# LKS_074DO.net
KiCad netlist of a schematic drawn in Altium Designer
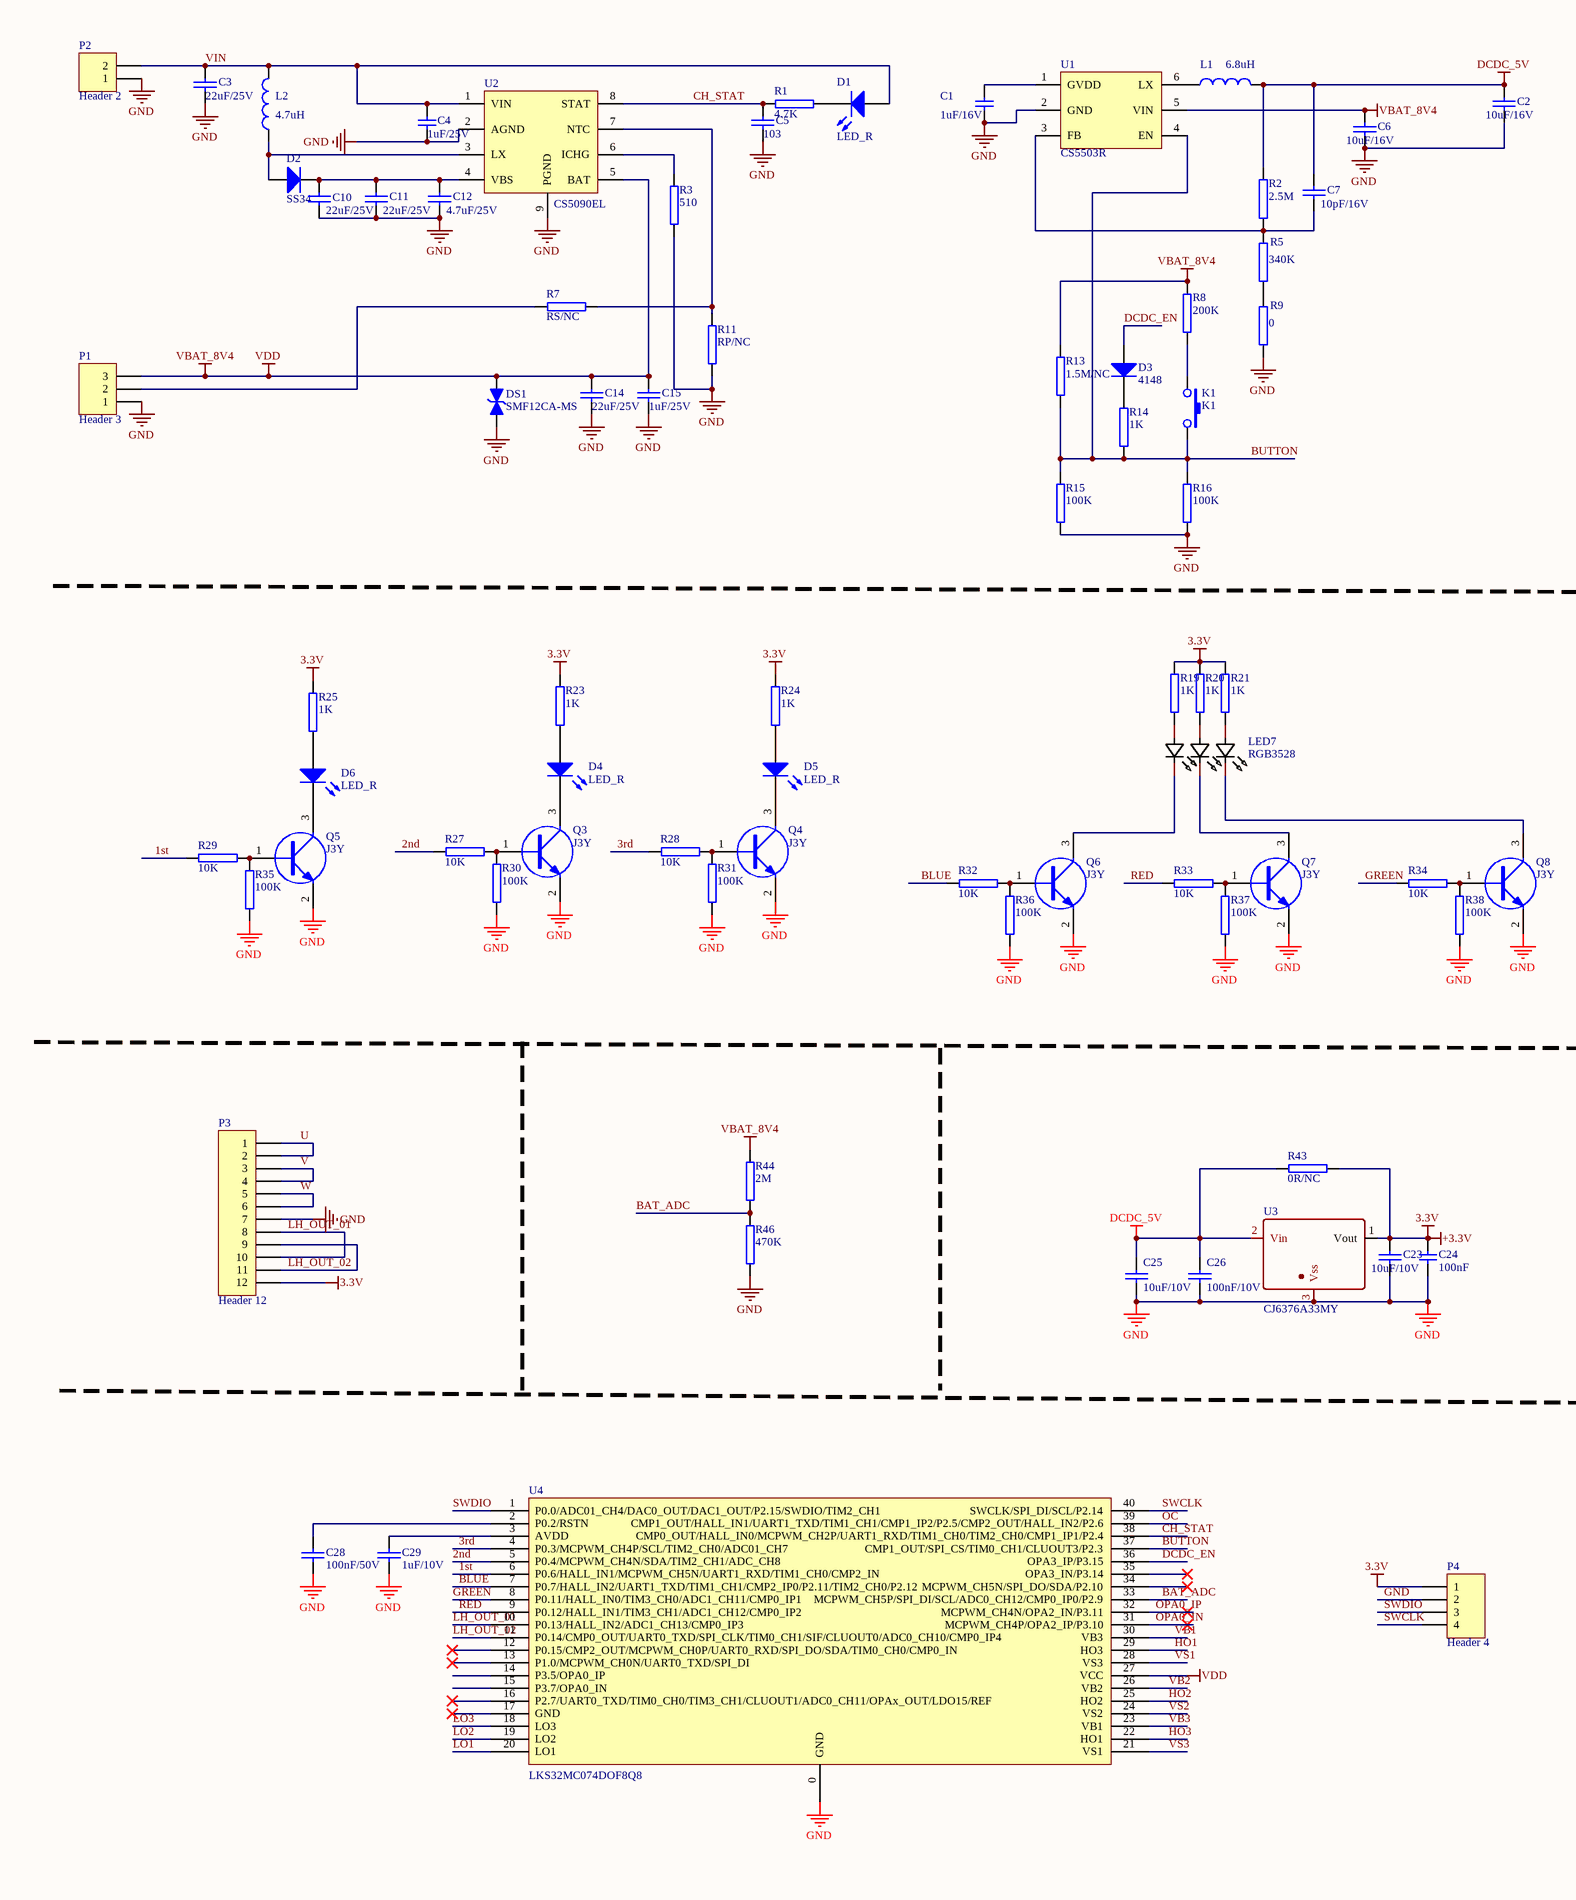
[diagram p0: LKS_074DO.SchDoc, left]
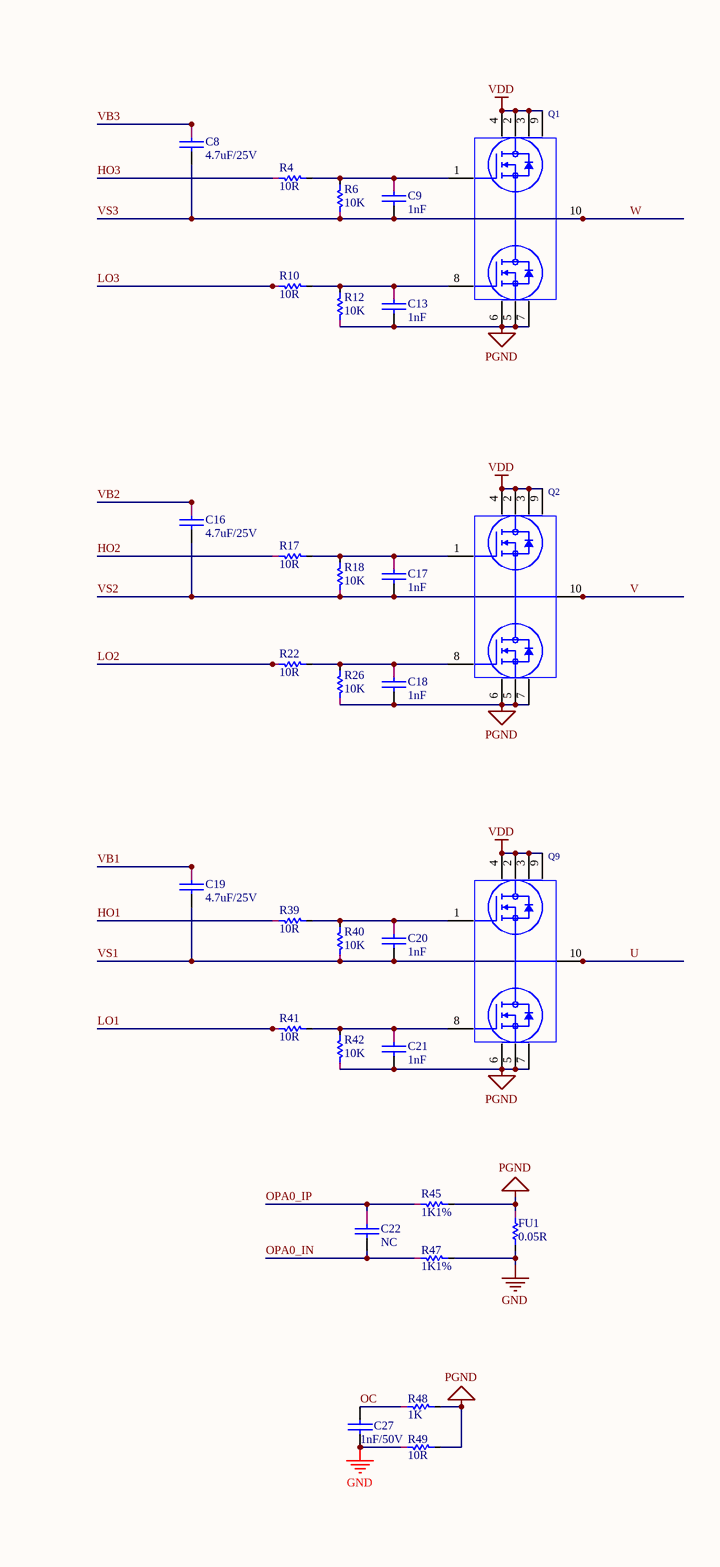
[diagram p1: LKS_074DO.SchDoc, right]

(export (version "E")
  (design (tool "Eeschema 10.0.6"))
  (components
    (comp (ref "C1") (value "1uF/16V") (footprint "C 0402_M") (libsource (lib "") (part "CAP_2")))
    (comp (ref "C2")
      (value "10uF/16V")
      (footprint "0805C")
      (description "Capacitor")
      (libsource (lib "") (part "CAP_1"))
    )
    (comp (ref "C3")
      (value "22uF/25V")
      (footprint "0805C")
      (description "Capacitor")
      (libsource (lib "") (part "CAP_1"))
    )
    (comp (ref "C4") (value "1uF/25V") (footprint "C 0402_M") (libsource (lib "") (part "CAP_2")))
    (comp (ref "C5")
      (value "103")
      (footprint "R 0402_M")
      (description "Capacitor")
      (libsource (lib "") (part "CAP_1"))
    )
    (comp (ref "C6")
      (value "10uF/16V")
      (footprint "0805C")
      (description "Capacitor")
      (libsource (lib "") (part "CAP_1"))
    )
    (comp (ref "C7")
      (value "10pF/16V")
      (footprint "C 0402_M")
      (description "Capacitor")
      (libsource (lib "") (part "CAP_1"))
    )
    (comp (ref "C8")
      (value "4.7uF/25V")
      (footprint "C 0603_M")
      (description "Capacitor")
      (libsource (lib "*") (part "CAP"))
    )
    (comp (ref "C9")
      (value "1nF")
      (footprint "C 0402_M")
      (description "Capacitor")
      (libsource (lib "*") (part "CAP"))
    )
    (comp (ref "C10")
      (value "22uF/25V")
      (footprint "0805C")
      (description "Capacitor")
      (libsource (lib "") (part "CAP_1"))
    )
    (comp (ref "C11")
      (value "22uF/25V")
      (footprint "0805C")
      (description "Capacitor")
      (libsource (lib "") (part "CAP_1"))
    )
    (comp (ref "C12")
      (value "4.7uF/25V")
      (footprint "C 0402_M")
      (description "Capacitor")
      (libsource (lib "") (part "CAP_1"))
    )
    (comp (ref "C13")
      (value "1nF")
      (footprint "C 0402_M")
      (description "Capacitor")
      (libsource (lib "*") (part "CAP"))
    )
    (comp (ref "C14")
      (value "22uF/25V")
      (footprint "0805C")
      (description "Capacitor")
      (libsource (lib "") (part "CAP_1"))
    )
    (comp (ref "C15")
      (value "1uF/25V")
      (footprint "C 0402_M")
      (description "Capacitor")
      (libsource (lib "") (part "CAP_1"))
    )
    (comp (ref "C16")
      (value "4.7uF/25V")
      (footprint "C 0603_M")
      (description "Capacitor")
      (libsource (lib "*") (part "CAP"))
    )
    (comp (ref "C17")
      (value "1nF")
      (footprint "C 0402_M")
      (description "Capacitor")
      (libsource (lib "*") (part "CAP"))
    )
    (comp (ref "C18")
      (value "1nF")
      (footprint "C 0402_M")
      (description "Capacitor")
      (libsource (lib "*") (part "CAP"))
    )
    (comp (ref "C19")
      (value "4.7uF/25V")
      (footprint "C 0603_M")
      (description "Capacitor")
      (libsource (lib "*") (part "CAP"))
    )
    (comp (ref "C20")
      (value "1nF")
      (footprint "C 0402_M")
      (description "Capacitor")
      (libsource (lib "*") (part "CAP"))
    )
    (comp (ref "C21")
      (value "1nF")
      (footprint "C 0402_M")
      (description "Capacitor")
      (libsource (lib "*") (part "CAP"))
    )
    (comp (ref "C22")
      (value "NC")
      (footprint "C 0402_M")
      (description "Capacitor")
      (libsource (lib "*") (part "CAP"))
    )
    (comp (ref "C23")
      (value "10uF/10V")
      (footprint "0805C")
      (description "Capacitor")
      (libsource (lib "") (part "CAP_1"))
    )
    (comp (ref "C24") (value "100nF") (footprint "C 0402_M") (libsource (lib "") (part "CAP_2")))
    (comp (ref "C25")
      (value "10uF/10V")
      (footprint "0805C")
      (description "Capacitor")
      (libsource (lib "") (part "CAP_1"))
    )
    (comp (ref "C26")
      (value "100nF/10V")
      (footprint "C 0402_M")
      (description "Capacitor")
      (libsource (lib "") (part "CAP_1"))
    )
    (comp (ref "C27")
      (value "1nF/50V")
      (footprint "C 0402_M")
      (description "Capacitor")
      (libsource (lib "*") (part "C"))
    )
    (comp (ref "C28")
      (value "100nF/50V")
      (footprint "C 0402_M")
      (description "Capacitor")
      (libsource (lib "*") (part "C"))
    )
    (comp (ref "C29")
      (value "1uF/10V")
      (footprint "0603")
      (description "Capacitor")
      (libsource (lib "*") (part "C"))
    )
    (comp (ref "D1") (value "LED_R") (footprint "0603-LED") (libsource (lib "PuXun1") (part "LED")))
    (comp (ref "D2")
      (value "SS34")
      (footprint "SOD123FL")
      (description "Default Diode")
      (fields (field (name "PUBLISHER") "Altium Limited"))
      (libsource (lib "LKS034DO_Motor_0520_1") (part "Diode"))
    )
    (comp (ref "D3")
      (value "4148")
      (footprint "SOD-323")
      (description "Default Diode")
      (fields (field (name "PUBLISHER") "Altium Limited"))
      (libsource (lib "LKS034DO_Motor_0520_1") (part "Diode"))
    )
    (comp (ref "D4") (value "LED_R") (footprint "0603-LED") (libsource (lib "PuXun1") (part "LED")))
    (comp (ref "D5") (value "LED_R") (footprint "0603-LED") (libsource (lib "PuXun1") (part "LED")))
    (comp (ref "D6") (value "LED_R") (footprint "0603-LED") (libsource (lib "PuXun1") (part "LED")))
    (comp (ref "DS1")
      (value "SMF12CA-MS")
      (footprint "SOD-123F")
      (description "12V/19.9V")
      (libsource (lib "*") (part "DIODE-3"))
    )
    (comp (ref "FU1") (value "0.05R") (footprint "R 0805_M") (libsource (lib "*") (part "RAS")))
    (comp (ref "K1") (value "K1") (footprint "Button3x4x2") (libsource (lib "SCHLIB_NEW") (part "K1")))
    (comp (ref "L1")
      (value "6.8uH")
      (footprint "SMD3X3")
      (description "Inductor")
      (fields (field (name "PUBLISHER") "Altium Limited"))
      (libsource (lib "Miscellaneous Devices") (part "Inductor"))
    )
    (comp (ref "L2")
      (value "4.7uH")
      (footprint "0420-L")
      (description "Inductor")
      (fields (field (name "PUBLISHER") "Altium Limited"))
      (libsource (lib "Miscellaneous Devices") (part "Inductor"))
    )
    (comp (ref "LED7")
      (value "RGB3528")
      (footprint "SMD3528-RGB")
      (libsource (lib "LKS074DO_BRUSH") (part "RGB5050"))
    )
    (comp (ref "P1")
      (value "Header 3")
      (footprint "X9827WRS-3P")
      (description "Header, 3-Pin")
      (fields (field (name "PUBLISHER") "Altium Limited"))
      (libsource (lib "Miscellaneous Connectors") (part "Header 3"))
    )
    (comp (ref "P2")
      (value "Header 2")
      (footprint "CONN_SMD_2P_0.6")
      (description "Header, 2-Pin")
      (fields (field (name "PUBLISHER") "Altium Limited"))
      (libsource (lib "Miscellaneous Connectors") (part "Header 2"))
    )
    (comp (ref "P3")
      (value "Header 12")
      (footprint "SMD-12")
      (description "Header, 12-Pin")
      (fields (field (name "PUBLISHER") "Altium Limited"))
      (libsource (lib "Miscellaneous Connectors") (part "Header 12"))
    )
    (comp (ref "P4")
      (value "Header 4")
      (footprint "HDR1X4")
      (description "Header, 4-Pin")
      (fields (field (name "PUBLISHER") "Altium Limited"))
      (libsource (lib "Miscellaneous Connectors") (part "Header 4"))
    )
    (comp (ref "Q1") (value "CJBM3020") (footprint "DFN-3X3_8") (libsource (lib "*") (part "CJBM3020")))
    (comp (ref "Q2") (value "CJBM3020") (footprint "DFN-3X3_8") (libsource (lib "*") (part "CJBM3020")))
    (comp (ref "Q3")
      (value "J3Y")
      (footprint "SOT-23")
      (description "NPN Transistor")
      (libsource (lib "*") (part "NPN"))
    )
    (comp (ref "Q4")
      (value "J3Y")
      (footprint "SOT-23")
      (description "NPN Transistor")
      (libsource (lib "*") (part "NPN"))
    )
    (comp (ref "Q5")
      (value "J3Y")
      (footprint "SOT-23")
      (description "NPN Transistor")
      (libsource (lib "*") (part "NPN"))
    )
    (comp (ref "Q6")
      (value "J3Y")
      (footprint "SOT-23")
      (description "NPN Transistor")
      (libsource (lib "*") (part "NPN"))
    )
    (comp (ref "Q7")
      (value "J3Y")
      (footprint "SOT-23")
      (description "NPN Transistor")
      (libsource (lib "*") (part "NPN"))
    )
    (comp (ref "Q8")
      (value "J3Y")
      (footprint "SOT-23")
      (description "NPN Transistor")
      (libsource (lib "*") (part "NPN"))
    )
    (comp (ref "Q9") (value "CJBM3020") (footprint "DFN-3X3_8") (libsource (lib "*") (part "CJBM3020")))
    (comp (ref "R1") (value "4.7K") (footprint "C 0402_M") (libsource (lib "*") (part "RES2_S")))
    (comp (ref "R2") (value "2.5M") (footprint "C 0402_M") (libsource (lib "*") (part "RES2_S")))
    (comp (ref "R3") (value "510") (footprint "R 0402_M") (libsource (lib "*") (part "RES2_S")))
    (comp (ref "R4") (value "10R") (footprint "R 0402_M") (libsource (lib "*") (part "RAS")))
    (comp (ref "R5") (value "340K") (footprint "C 0402_M") (libsource (lib "*") (part "RES2_S")))
    (comp (ref "R6") (value "10K") (footprint "R 0402_M") (libsource (lib "*") (part "RAS")))
    (comp (ref "R7") (value "RS/NC") (footprint "R 0402_M") (libsource (lib "*") (part "RES2_S")))
    (comp (ref "R8") (value "200K") (footprint "C 0402_M") (libsource (lib "*") (part "RES2_S")))
    (comp (ref "R9") (value "0") (footprint "C 0402_M") (libsource (lib "*") (part "RES2_S")))
    (comp (ref "R10") (value "10R") (footprint "R 0402_M") (libsource (lib "*") (part "RAS")))
    (comp (ref "R11") (value "RP/NC") (footprint "R 0402_M") (libsource (lib "*") (part "RES2_S")))
    (comp (ref "R12") (value "10K") (footprint "R 0402_M") (libsource (lib "*") (part "RAS")))
    (comp (ref "R13") (value "1.5M/NC") (footprint "C 0402_M") (libsource (lib "*") (part "RES2_S")))
    (comp (ref "R14") (value "1K") (footprint "C 0402_M") (libsource (lib "*") (part "RES2_S")))
    (comp (ref "R15") (value "100K") (footprint "C 0402_M") (libsource (lib "*") (part "RES2_S")))
    (comp (ref "R16") (value "100K") (footprint "C 0402_M") (libsource (lib "*") (part "RES2_S")))
    (comp (ref "R17") (value "10R") (footprint "R 0402_M") (libsource (lib "*") (part "RAS")))
    (comp (ref "R18") (value "10K") (footprint "R 0402_M") (libsource (lib "*") (part "RAS")))
    (comp (ref "R19") (value "1K") (footprint "C 0402_M") (libsource (lib "*") (part "RES2_S")))
    (comp (ref "R20") (value "1K") (footprint "C 0402_M") (libsource (lib "*") (part "RES2_S")))
    (comp (ref "R21") (value "1K") (footprint "C 0402_M") (libsource (lib "*") (part "RES2_S")))
    (comp (ref "R22") (value "10R") (footprint "R 0402_M") (libsource (lib "*") (part "RAS")))
    (comp (ref "R23") (value "1K") (footprint "C 0402_M") (libsource (lib "*") (part "RES2_S")))
    (comp (ref "R24") (value "1K") (footprint "C 0402_M") (libsource (lib "*") (part "RES2_S")))
    (comp (ref "R25") (value "1K") (footprint "C 0402_M") (libsource (lib "*") (part "RES2_S")))
    (comp (ref "R26") (value "10K") (footprint "R 0402_M") (libsource (lib "*") (part "RAS")))
    (comp (ref "R27") (value "10K") (footprint "C 0402_M") (libsource (lib "*") (part "RES2_S")))
    (comp (ref "R28") (value "10K") (footprint "C 0402_M") (libsource (lib "*") (part "RES2_S")))
    (comp (ref "R29") (value "10K") (footprint "C 0402_M") (libsource (lib "*") (part "RES2_S")))
    (comp (ref "R30") (value "100K") (footprint "C 0402_M") (libsource (lib "*") (part "RES2_S")))
    (comp (ref "R31") (value "100K") (footprint "C 0402_M") (libsource (lib "*") (part "RES2_S")))
    (comp (ref "R32") (value "10K") (footprint "C 0402_M") (libsource (lib "*") (part "RES2_S")))
    (comp (ref "R33") (value "10K") (footprint "C 0402_M") (libsource (lib "*") (part "RES2_S")))
    (comp (ref "R34") (value "10K") (footprint "C 0402_M") (libsource (lib "*") (part "RES2_S")))
    (comp (ref "R35") (value "100K") (footprint "C 0402_M") (libsource (lib "*") (part "RES2_S")))
    (comp (ref "R36") (value "100K") (footprint "C 0402_M") (libsource (lib "*") (part "RES2_S")))
    (comp (ref "R37") (value "100K") (footprint "C 0402_M") (libsource (lib "*") (part "RES2_S")))
    (comp (ref "R38") (value "100K") (footprint "C 0402_M") (libsource (lib "*") (part "RES2_S")))
    (comp (ref "R39") (value "10R") (footprint "R 0402_M") (libsource (lib "*") (part "RAS")))
    (comp (ref "R40") (value "10K") (footprint "R 0402_M") (libsource (lib "*") (part "RAS")))
    (comp (ref "R41") (value "10R") (footprint "R 0402_M") (libsource (lib "*") (part "RAS")))
    (comp (ref "R42") (value "10K") (footprint "R 0402_M") (libsource (lib "*") (part "RAS")))
    (comp (ref "R43") (value "0R/NC") (footprint "R 0805_M") (libsource (lib "*") (part "RES2_S")))
    (comp (ref "R44") (value "2M") (footprint "C 0402_M") (libsource (lib "*") (part "RES2_S")))
    (comp (ref "R45") (value "1K1%") (footprint "R 0402_M") (libsource (lib "*") (part "RAS")))
    (comp (ref "R46") (value "470K") (footprint "C 0402_M") (libsource (lib "*") (part "RES2_S")))
    (comp (ref "R47") (value "1K1%") (footprint "R 0402_M") (libsource (lib "*") (part "RAS")))
    (comp (ref "R48") (value "1K") (footprint "R 0402_M") (libsource (lib "*") (part "RAS")))
    (comp (ref "R49") (value "10R") (footprint "R 0402_M") (libsource (lib "*") (part "RAS")))
    (comp (ref "U1")
      (value "CS5503R")
      (footprint "SOT23-6L")
      (libsource (lib "LKS034DO_Motor_0520_1") (part "CS5503R"))
    )
    (comp (ref "U2")
      (value "CS5090EL")
      (footprint "DFN2X2_8_0.5")
      (libsource (lib "LKS034DO_Motor_0520_1") (part "CS5090EL"))
    )
    (comp (ref "U3")
      (value "CJ6376A33MY")
      (footprint "SOT-23")
      (libsource (lib "LKS034DO_Motor_0520_1") (part "78L15"))
    )
    (comp (ref "U4")
      (value "LKS32MC074DOF8Q8")
      (footprint "QFN40")
      (description "芯片")
      (libsource (lib "Q_LINKO_V1.0") (part "LKS32MC074DF8Q8"))
    )
  )
  (nets
    (net (code "1") (name "+3.3V") (class "Default")
      (node (ref "C23") (pin "2") (pinfunction "2_2") (pintype "passive"))
      (node (ref "C24") (pin "1") (pinfunction "1_1") (pintype "passive"))
      (node (ref "P3") (pin "12") (pinfunction "12_12") (pintype "passive"))
      (node (ref "P4") (pin "1") (pinfunction "1_1") (pintype "passive"))
      (node (ref "R19") (pin "2") (pinfunction "2_2") (pintype "passive"))
      (node (ref "R20") (pin "2") (pinfunction "2_2") (pintype "passive"))
      (node (ref "R21") (pin "2") (pinfunction "2_2") (pintype "passive"))
      (node (ref "R23") (pin "2") (pinfunction "2_2") (pintype "passive"))
      (node (ref "R24") (pin "2") (pinfunction "2_2") (pintype "passive"))
      (node (ref "R25") (pin "2") (pinfunction "2_2") (pintype "passive"))
      (node (ref "R43") (pin "2") (pinfunction "2_2") (pintype "passive"))
      (node (ref "U3") (pin "1") (pinfunction "Vout_1") (pintype "passive"))
    )
    (net (code "2") (name "/1st") (class "Default")
      (node (ref "R29") (pin "2") (pinfunction "2_2") (pintype "passive"))
      (node (ref "U4") (pin "6") (pinfunction "P0.6/HALL_IN1/MCPWM_CH5N/UART1_RXD/TIM1_CH0/CMP2_IN_6") (pintype "passive"))
    )
    (net (code "3") (name "/2nd") (class "Default")
      (node (ref "R27") (pin "2") (pinfunction "2_2") (pintype "passive"))
      (node (ref "U4") (pin "5") (pinfunction "P0.4/MCPWM_CH4N/SDA/TIM2_CH1/ADC_CH8_5") (pintype "passive"))
    )
    (net (code "4") (name "/3rd") (class "Default")
      (node (ref "R28") (pin "2") (pinfunction "2_2") (pintype "passive"))
      (node (ref "U4") (pin "4") (pinfunction "P0.3/MCPWM_CH4P/SCL/TIM2_CH0/ADC01_CH7_4") (pintype "passive"))
    )
    (net (code "5") (name "/BAT_ADC") (class "Default")
      (node (ref "R44") (pin "2") (pinfunction "2_2") (pintype "passive"))
      (node (ref "R46") (pin "1") (pinfunction "1_1") (pintype "passive"))
      (node (ref "U4") (pin "33") (pinfunction "MCPWM_CH5P/SPI_DI/SCL/ADC0_CH12/CMP0_IP0/P2.9_33") (pintype "passive"))
    )
    (net (code "6") (name "/BLUE") (class "Default")
      (node (ref "R32") (pin "2") (pinfunction "2_2") (pintype "passive"))
      (node (ref "U4") (pin "7") (pinfunction "P0.7/HALL_IN2/UART1_TXD/TIM1_CH1/CMP2_IP0/P2.11/TIM2_CH0/P2.12_7") (pintype "passive"))
    )
    (net (code "7") (name "/BUTTON") (class "Default")
      (node (ref "K1") (pin "2") (pintype "passive"))
      (node (ref "R13") (pin "2") (pinfunction "2_2") (pintype "passive"))
      (node (ref "R14") (pin "2") (pinfunction "2_2") (pintype "passive"))
      (node (ref "R15") (pin "2") (pinfunction "2_2") (pintype "passive"))
      (node (ref "R16") (pin "1") (pinfunction "1_1") (pintype "passive"))
      (node (ref "U1") (pin "4") (pinfunction "EN_4") (pintype "passive"))
      (node (ref "U4") (pin "37") (pinfunction "CMP1_OUT/SPI_CS/TIM0_CH1/CLUOUT3/P2.3_37") (pintype "passive"))
    )
    (net (code "8") (name "/CH_STAT") (class "Default")
      (node (ref "C5") (pin "2") (pinfunction "2_2") (pintype "passive"))
      (node (ref "R1") (pin "1") (pinfunction "1_1") (pintype "passive"))
      (node (ref "U2") (pin "8") (pinfunction "STAT_8") (pintype "passive"))
      (node (ref "U4") (pin "38") (pinfunction "CMP0_OUT/HALL_IN0/MCPWM_CH2P/UART1_RXD/TIM1_CH0/TIM2_CH0/CMP1_IP1/P2.4_38") (pintype "passive"))
    )
    (net (code "9") (name "/DCDC_EN") (class "Default")
      (node (ref "D3") (pin "1") (pinfunction "A_1") (pintype "passive"))
      (node (ref "U4") (pin "36") (pinfunction "OPA3_IP/P3.15_36") (pintype "passive"))
    )
    (net (code "10") (name "/GREEN") (class "Default")
      (node (ref "R34") (pin "2") (pinfunction "2_2") (pintype "passive"))
      (node (ref "U4") (pin "8") (pinfunction "P0.11/HALL_IN0/TIM3_CH0/ADC1_CH11/CMP0_IP1_8") (pintype "passive"))
    )
    (net (code "11") (name "/HO1") (class "Default")
      (node (ref "R39") (pin "2") (pinfunction "2_2") (pintype "passive"))
      (node (ref "U4") (pin "29") (pinfunction "HO3_29") (pintype "passive"))
    )
    (net (code "12") (name "/HO2") (class "Default")
      (node (ref "R17") (pin "2") (pinfunction "2_2") (pintype "passive"))
      (node (ref "U4") (pin "25") (pinfunction "HO2_25") (pintype "passive"))
    )
    (net (code "13") (name "/HO3") (class "Default")
      (node (ref "R4") (pin "2") (pinfunction "2_2") (pintype "passive"))
      (node (ref "U4") (pin "22") (pinfunction "HO1_22") (pintype "passive"))
    )
    (net (code "14") (name "/LH_OUT_01") (class "Default")
      (node (ref "P3") (pin "10") (pinfunction "10_10") (pintype "passive"))
      (node (ref "P3") (pin "8") (pinfunction "8_8") (pintype "passive"))
      (node (ref "U4") (pin "10") (pinfunction "P0.13/HALL_IN2/ADC1_CH13/CMP0_IP3_10") (pintype "passive"))
    )
    (net (code "15") (name "/LH_OUT_02") (class "Default")
      (node (ref "P3") (pin "11") (pinfunction "11_11") (pintype "passive"))
      (node (ref "P3") (pin "9") (pinfunction "9_9") (pintype "passive"))
      (node (ref "U4") (pin "11") (pinfunction "P0.14/CMP0_OUT/UART0_TXD/SPI_CLK/TIM0_CH1/SIF/CLUOUT0/ADC0_CH10/CMP0_IP4_11") (pintype "passive"))
    )
    (net (code "16") (name "/LO1") (class "Default")
      (node (ref "R41") (pin "2") (pinfunction "2_2") (pintype "passive"))
      (node (ref "U4") (pin "20") (pinfunction "LO1_20") (pintype "passive"))
    )
    (net (code "17") (name "/LO2") (class "Default")
      (node (ref "R22") (pin "2") (pinfunction "2_2") (pintype "passive"))
      (node (ref "U4") (pin "19") (pinfunction "LO2_19") (pintype "passive"))
    )
    (net (code "18") (name "/LO3") (class "Default")
      (node (ref "R10") (pin "2") (pinfunction "2_2") (pintype "passive"))
      (node (ref "U4") (pin "18") (pinfunction "LO3_18") (pintype "passive"))
    )
    (net (code "19") (name "/OC") (class "Default")
      (node (ref "C27") (pin "2") (pinfunction "2_2") (pintype "passive"))
      (node (ref "R48") (pin "2") (pinfunction "2_2") (pintype "passive"))
      (node (ref "U4") (pin "39") (pinfunction "CMP1_OUT/HALL_IN1/UART1_TXD/TIM1_CH1/CMP1_IP2/P2.5/CMP2_OUT/HALL_IN2/P2.6_39") (pintype "passive"))
    )
    (net (code "20") (name "/OPA0_IN") (class "Default")
      (node (ref "C22") (pin "1") (pinfunction "1_1") (pintype "passive"))
      (node (ref "R47") (pin "2") (pinfunction "2_2") (pintype "passive"))
      (node (ref "U4") (pin "31") (pinfunction "MCPWM_CH4P/OPA2_IP/P3.10_31") (pintype "passive"))
    )
    (net (code "21") (name "/OPA0_IP") (class "Default")
      (node (ref "C22") (pin "2") (pinfunction "2_2") (pintype "passive"))
      (node (ref "R45") (pin "2") (pinfunction "2_2") (pintype "passive"))
      (node (ref "U4") (pin "32") (pinfunction "MCPWM_CH4N/OPA2_IN/P3.11_32") (pintype "passive"))
    )
    (net (code "22") (name "/RED") (class "Default")
      (node (ref "R33") (pin "2") (pinfunction "2_2") (pintype "passive"))
      (node (ref "U4") (pin "9") (pinfunction "P0.12/HALL_IN1/TIM3_CH1/ADC1_CH12/CMP0_IP2_9") (pintype "passive"))
    )
    (net (code "23") (name "/SWCLK") (class "Default")
      (node (ref "P4") (pin "4") (pinfunction "4_4") (pintype "passive"))
      (node (ref "U4") (pin "40") (pinfunction "SWCLK/SPI_DI/SCL/P2.14_40") (pintype "passive"))
    )
    (net (code "24") (name "/SWDIO") (class "Default")
      (node (ref "P4") (pin "3") (pinfunction "3_3") (pintype "passive"))
      (node (ref "U4") (pin "1") (pinfunction "P0.0/ADC01_CH4/DAC0_OUT/DAC1_OUT/P2.15/SWDIO/TIM2_CH1_1") (pintype "passive"))
    )
    (net (code "25") (name "/U") (class "Default")
      (node (ref "C19") (pin "1") (pinfunction "1_1") (pintype "passive"))
      (node (ref "C20") (pin "1") (pinfunction "1_1") (pintype "passive"))
      (node (ref "P3") (pin "1") (pinfunction "1_1") (pintype "passive"))
      (node (ref "P3") (pin "2") (pinfunction "2_2") (pintype "passive"))
      (node (ref "Q9") (pin "10") (pinfunction "S1/D2_10") (pintype "passive"))
      (node (ref "R40") (pin "2") (pinfunction "2_2") (pintype "passive"))
      (node (ref "U4") (pin "28") (pinfunction "VS3_28") (pintype "passive"))
    )
    (net (code "26") (name "/V") (class "Default")
      (node (ref "C16") (pin "1") (pinfunction "1_1") (pintype "passive"))
      (node (ref "C17") (pin "1") (pinfunction "1_1") (pintype "passive"))
      (node (ref "P3") (pin "3") (pinfunction "3_3") (pintype "passive"))
      (node (ref "P3") (pin "4") (pinfunction "4_4") (pintype "passive"))
      (node (ref "Q2") (pin "10") (pinfunction "S1/D2_10") (pintype "passive"))
      (node (ref "R18") (pin "2") (pinfunction "2_2") (pintype "passive"))
      (node (ref "U4") (pin "24") (pinfunction "VS2_24") (pintype "passive"))
    )
    (net (code "27") (name "/VB1") (class "Default")
      (node (ref "C19") (pin "2") (pinfunction "2_2") (pintype "passive"))
      (node (ref "U4") (pin "30") (pinfunction "VB3_30") (pintype "passive"))
    )
    (net (code "28") (name "/VB2") (class "Default")
      (node (ref "C16") (pin "2") (pinfunction "2_2") (pintype "passive"))
      (node (ref "U4") (pin "26") (pinfunction "VB2_26") (pintype "passive"))
    )
    (net (code "29") (name "/VB3") (class "Default")
      (node (ref "C8") (pin "2") (pinfunction "2_2") (pintype "passive"))
      (node (ref "U4") (pin "23") (pinfunction "VB1_23") (pintype "passive"))
    )
    (net (code "30") (name "/VIN") (class "Default")
      (node (ref "C3") (pin "2") (pinfunction "2_2") (pintype "passive"))
      (node (ref "C4") (pin "1") (pinfunction "1_1") (pintype "passive"))
      (node (ref "D1") (pin "1") (pinfunction "A_1") (pintype "passive"))
      (node (ref "L2") (pin "2") (pinfunction "2_2") (pintype "passive"))
      (node (ref "P2") (pin "2") (pinfunction "2_2") (pintype "passive"))
      (node (ref "U2") (pin "1") (pinfunction "VIN_1") (pintype "passive"))
    )
    (net (code "31") (name "/VS3") (class "Default")
      (node (ref "C8") (pin "1") (pinfunction "1_1") (pintype "passive"))
      (node (ref "C9") (pin "1") (pinfunction "1_1") (pintype "passive"))
      (node (ref "P3") (pin "5") (pinfunction "5_5") (pintype "passive"))
      (node (ref "P3") (pin "6") (pinfunction "6_6") (pintype "passive"))
      (node (ref "Q1") (pin "10") (pinfunction "S1/D2_10") (pintype "passive"))
      (node (ref "R6") (pin "2") (pinfunction "2_2") (pintype "passive"))
      (node (ref "U4") (pin "21") (pinfunction "VS1_21") (pintype "passive"))
    )
    (net (code "32") (name "DCDC_5V") (class "Default")
      (node (ref "C2") (pin "2") (pinfunction "2_2") (pintype "passive"))
      (node (ref "C25") (pin "2") (pinfunction "2_2") (pintype "passive"))
      (node (ref "C26") (pin "1") (pinfunction "1_1") (pintype "passive"))
      (node (ref "C7") (pin "2") (pinfunction "2_2") (pintype "passive"))
      (node (ref "L1") (pin "2") (pinfunction "2_2") (pintype "passive"))
      (node (ref "R2") (pin "1") (pinfunction "1_1") (pintype "passive"))
      (node (ref "R43") (pin "1") (pinfunction "1_1") (pintype "passive"))
      (node (ref "U3") (pin "2") (pinfunction "Vin_2") (pintype "passive"))
    )
    (net (code "33") (name "GND") (class "Default")
      (node (ref "C1") (pin "1") (pinfunction "1_1") (pintype "passive"))
      (node (ref "C10") (pin "1") (pinfunction "1_1") (pintype "passive"))
      (node (ref "C11") (pin "1") (pinfunction "1_1") (pintype "passive"))
      (node (ref "C12") (pin "1") (pinfunction "1_1") (pintype "passive"))
      (node (ref "C14") (pin "1") (pinfunction "1_1") (pintype "passive"))
      (node (ref "C15") (pin "1") (pinfunction "1_1") (pintype "passive"))
      (node (ref "C2") (pin "1") (pinfunction "1_1") (pintype "passive"))
      (node (ref "C23") (pin "1") (pinfunction "1_1") (pintype "passive"))
      (node (ref "C24") (pin "2") (pinfunction "2_2") (pintype "passive"))
      (node (ref "C25") (pin "1") (pinfunction "1_1") (pintype "passive"))
      (node (ref "C26") (pin "2") (pinfunction "2_2") (pintype "passive"))
      (node (ref "C27") (pin "1") (pinfunction "1_1") (pintype "passive"))
      (node (ref "C28") (pin "2") (pinfunction "2_2") (pintype "passive"))
      (node (ref "C29") (pin "1") (pinfunction "1_1") (pintype "passive"))
      (node (ref "C3") (pin "1") (pinfunction "1_1") (pintype "passive"))
      (node (ref "C4") (pin "2") (pinfunction "2_2") (pintype "passive"))
      (node (ref "C5") (pin "1") (pinfunction "1_1") (pintype "passive"))
      (node (ref "C6") (pin "1") (pinfunction "1_1") (pintype "passive"))
      (node (ref "DS1") (pin "2") (pinfunction "K_2") (pintype "passive"))
      (node (ref "FU1") (pin "1") (pinfunction "1_1") (pintype "passive"))
      (node (ref "P1") (pin "1") (pinfunction "1_1") (pintype "passive"))
      (node (ref "P2") (pin "1") (pinfunction "1_1") (pintype "passive"))
      (node (ref "P3") (pin "7") (pinfunction "7_7") (pintype "passive"))
      (node (ref "P4") (pin "2") (pinfunction "2_2") (pintype "passive"))
      (node (ref "Q3") (pin "2") (pinfunction "E_2") (pintype "passive"))
      (node (ref "Q4") (pin "2") (pinfunction "E_2") (pintype "passive"))
      (node (ref "Q5") (pin "2") (pinfunction "E_2") (pintype "passive"))
      (node (ref "Q6") (pin "2") (pinfunction "E_2") (pintype "passive"))
      (node (ref "Q7") (pin "2") (pinfunction "E_2") (pintype "passive"))
      (node (ref "Q8") (pin "2") (pinfunction "E_2") (pintype "passive"))
      (node (ref "R11") (pin "2") (pinfunction "2_2") (pintype "passive"))
      (node (ref "R15") (pin "1") (pinfunction "1_1") (pintype "passive"))
      (node (ref "R16") (pin "2") (pinfunction "2_2") (pintype "passive"))
      (node (ref "R3") (pin "2") (pinfunction "2_2") (pintype "passive"))
      (node (ref "R30") (pin "2") (pinfunction "2_2") (pintype "passive"))
      (node (ref "R31") (pin "2") (pinfunction "2_2") (pintype "passive"))
      (node (ref "R35") (pin "2") (pinfunction "2_2") (pintype "passive"))
      (node (ref "R36") (pin "2") (pinfunction "2_2") (pintype "passive"))
      (node (ref "R37") (pin "2") (pinfunction "2_2") (pintype "passive"))
      (node (ref "R38") (pin "2") (pinfunction "2_2") (pintype "passive"))
      (node (ref "R46") (pin "2") (pinfunction "2_2") (pintype "passive"))
      (node (ref "R47") (pin "1") (pinfunction "1_1") (pintype "passive"))
      (node (ref "R49") (pin "2") (pinfunction "2_2") (pintype "passive"))
      (node (ref "R9") (pin "2") (pinfunction "2_2") (pintype "passive"))
      (node (ref "U1") (pin "2") (pinfunction "GND_2") (pintype "passive"))
      (node (ref "U2") (pin "2") (pinfunction "AGND_2") (pintype "passive"))
      (node (ref "U2") (pin "9") (pinfunction "PGND_9") (pintype "passive"))
      (node (ref "U3") (pin "3") (pinfunction "Vss_3") (pintype "passive"))
      (node (ref "U4") (pin "0") (pinfunction "GND_0") (pintype "passive"))
    )
    (net (code "34") (name "Net-(D1-K)") (class "Default")
      (node (ref "D1") (pin "2") (pinfunction "K_2") (pintype "passive"))
      (node (ref "R1") (pin "2") (pinfunction "2_2") (pintype "passive"))
    )
    (net (code "35") (name "Net-(D2-A)") (class "Default")
      (node (ref "D2") (pin "1") (pinfunction "A_1") (pintype "passive"))
      (node (ref "L2") (pin "1") (pinfunction "1_1") (pintype "passive"))
      (node (ref "U2") (pin "3") (pinfunction "LX_3") (pintype "passive"))
    )
    (net (code "36") (name "Net-(D2-K)") (class "Default")
      (node (ref "C10") (pin "2") (pinfunction "2_2") (pintype "passive"))
      (node (ref "C11") (pin "2") (pinfunction "2_2") (pintype "passive"))
      (node (ref "C12") (pin "2") (pinfunction "2_2") (pintype "passive"))
      (node (ref "D2") (pin "2") (pinfunction "K_2") (pintype "passive"))
      (node (ref "U2") (pin "4") (pinfunction "VBS_4") (pintype "passive"))
    )
    (net (code "37") (name "Net-(D3-K)") (class "Default")
      (node (ref "D3") (pin "2") (pinfunction "K_2") (pintype "passive"))
      (node (ref "R14") (pin "1") (pinfunction "1_1") (pintype "passive"))
    )
    (net (code "38") (name "Net-(D4-A)") (class "Default")
      (node (ref "D4") (pin "1") (pinfunction "A_1") (pintype "passive"))
      (node (ref "R23") (pin "1") (pinfunction "1_1") (pintype "passive"))
    )
    (net (code "39") (name "Net-(D4-K)") (class "Default")
      (node (ref "D4") (pin "2") (pinfunction "K_2") (pintype "passive"))
      (node (ref "Q3") (pin "3") (pinfunction "C_3") (pintype "passive"))
    )
    (net (code "40") (name "Net-(D5-A)") (class "Default")
      (node (ref "D5") (pin "1") (pinfunction "A_1") (pintype "passive"))
      (node (ref "R24") (pin "1") (pinfunction "1_1") (pintype "passive"))
    )
    (net (code "41") (name "Net-(D5-K)") (class "Default")
      (node (ref "D5") (pin "2") (pinfunction "K_2") (pintype "passive"))
      (node (ref "Q4") (pin "3") (pinfunction "C_3") (pintype "passive"))
    )
    (net (code "42") (name "Net-(D6-A)") (class "Default")
      (node (ref "D6") (pin "1") (pinfunction "A_1") (pintype "passive"))
      (node (ref "R25") (pin "1") (pinfunction "1_1") (pintype "passive"))
    )
    (net (code "43") (name "Net-(D6-K)") (class "Default")
      (node (ref "D6") (pin "2") (pinfunction "K_2") (pintype "passive"))
      (node (ref "Q5") (pin "3") (pinfunction "C_3") (pintype "passive"))
    )
    (net (code "44") (name "Net-(K1-Pad1)") (class "Default")
      (node (ref "K1") (pin "1") (pintype "passive"))
      (node (ref "R8") (pin "1") (pinfunction "1_1") (pintype "passive"))
    )
    (net (code "45") (name "Net-(LED7-+-Pad4)") (class "Default")
      (node (ref "LED7") (pin "4") (pinfunction "+_4") (pintype "passive"))
      (node (ref "R21") (pin "1") (pinfunction "1_1") (pintype "passive"))
    )
    (net (code "46") (name "Net-(LED7-+-Pad5)") (class "Default")
      (node (ref "LED7") (pin "5") (pinfunction "+_5") (pintype "passive"))
      (node (ref "R20") (pin "1") (pinfunction "1_1") (pintype "passive"))
    )
    (net (code "47") (name "Net-(LED7-+-Pad6)") (class "Default")
      (node (ref "LED7") (pin "6") (pinfunction "+_6") (pintype "passive"))
      (node (ref "R19") (pin "1") (pinfunction "1_1") (pintype "passive"))
    )
    (net (code "48") (name "Net-(P1-Pad2)") (class "Default")
      (node (ref "P1") (pin "2") (pinfunction "2_2") (pintype "passive"))
      (node (ref "R7") (pin "1") (pinfunction "1_1") (pintype "passive"))
    )
    (net (code "49") (name "Net-(Q1-G1)") (class "Default")
      (node (ref "C9") (pin "2") (pinfunction "2_2") (pintype "passive"))
      (node (ref "Q1") (pin "1") (pinfunction "G1_1") (pintype "passive"))
      (node (ref "R4") (pin "1") (pinfunction "1_1") (pintype "passive"))
      (node (ref "R6") (pin "1") (pinfunction "1_1") (pintype "passive"))
    )
    (net (code "50") (name "Net-(Q1-G2)") (class "Default")
      (node (ref "C13") (pin "2") (pinfunction "2_2") (pintype "passive"))
      (node (ref "Q1") (pin "8") (pinfunction "G2_8") (pintype "passive"))
      (node (ref "R10") (pin "1") (pinfunction "1_1") (pintype "passive"))
      (node (ref "R12") (pin "1") (pinfunction "1_1") (pintype "passive"))
    )
    (net (code "51") (name "Net-(Q2-G1)") (class "Default")
      (node (ref "C17") (pin "2") (pinfunction "2_2") (pintype "passive"))
      (node (ref "Q2") (pin "1") (pinfunction "G1_1") (pintype "passive"))
      (node (ref "R17") (pin "1") (pinfunction "1_1") (pintype "passive"))
      (node (ref "R18") (pin "1") (pinfunction "1_1") (pintype "passive"))
    )
    (net (code "52") (name "Net-(Q2-G2)") (class "Default")
      (node (ref "C18") (pin "2") (pinfunction "2_2") (pintype "passive"))
      (node (ref "Q2") (pin "8") (pinfunction "G2_8") (pintype "passive"))
      (node (ref "R22") (pin "1") (pinfunction "1_1") (pintype "passive"))
      (node (ref "R26") (pin "1") (pinfunction "1_1") (pintype "passive"))
    )
    (net (code "53") (name "Net-(Q3-B)") (class "Default")
      (node (ref "Q3") (pin "1") (pinfunction "B_1") (pintype "passive"))
      (node (ref "R27") (pin "1") (pinfunction "1_1") (pintype "passive"))
      (node (ref "R30") (pin "1") (pinfunction "1_1") (pintype "passive"))
    )
    (net (code "54") (name "Net-(Q4-B)") (class "Default")
      (node (ref "Q4") (pin "1") (pinfunction "B_1") (pintype "passive"))
      (node (ref "R28") (pin "1") (pinfunction "1_1") (pintype "passive"))
      (node (ref "R31") (pin "1") (pinfunction "1_1") (pintype "passive"))
    )
    (net (code "55") (name "Net-(Q5-B)") (class "Default")
      (node (ref "Q5") (pin "1") (pinfunction "B_1") (pintype "passive"))
      (node (ref "R29") (pin "1") (pinfunction "1_1") (pintype "passive"))
      (node (ref "R35") (pin "1") (pinfunction "1_1") (pintype "passive"))
    )
    (net (code "56") (name "Net-(Q6-B)") (class "Default")
      (node (ref "Q6") (pin "1") (pinfunction "B_1") (pintype "passive"))
      (node (ref "R32") (pin "1") (pinfunction "1_1") (pintype "passive"))
      (node (ref "R36") (pin "1") (pinfunction "1_1") (pintype "passive"))
    )
    (net (code "57") (name "Net-(Q6-C)") (class "Default")
      (node (ref "LED7") (pin "3") (pinfunction "-_3") (pintype "passive"))
      (node (ref "Q6") (pin "3") (pinfunction "C_3") (pintype "passive"))
    )
    (net (code "58") (name "Net-(Q7-B)") (class "Default")
      (node (ref "Q7") (pin "1") (pinfunction "B_1") (pintype "passive"))
      (node (ref "R33") (pin "1") (pinfunction "1_1") (pintype "passive"))
      (node (ref "R37") (pin "1") (pinfunction "1_1") (pintype "passive"))
    )
    (net (code "59") (name "Net-(Q7-C)") (class "Default")
      (node (ref "LED7") (pin "2") (pinfunction "-_2") (pintype "passive"))
      (node (ref "Q7") (pin "3") (pinfunction "C_3") (pintype "passive"))
    )
    (net (code "60") (name "Net-(Q8-B)") (class "Default")
      (node (ref "Q8") (pin "1") (pinfunction "B_1") (pintype "passive"))
      (node (ref "R34") (pin "1") (pinfunction "1_1") (pintype "passive"))
      (node (ref "R38") (pin "1") (pinfunction "1_1") (pintype "passive"))
    )
    (net (code "61") (name "Net-(Q8-C)") (class "Default")
      (node (ref "LED7") (pin "1") (pinfunction "-_1") (pintype "passive"))
      (node (ref "Q8") (pin "3") (pinfunction "C_3") (pintype "passive"))
    )
    (net (code "62") (name "Net-(Q9-G1)") (class "Default")
      (node (ref "C20") (pin "2") (pinfunction "2_2") (pintype "passive"))
      (node (ref "Q9") (pin "1") (pinfunction "G1_1") (pintype "passive"))
      (node (ref "R39") (pin "1") (pinfunction "1_1") (pintype "passive"))
      (node (ref "R40") (pin "1") (pinfunction "1_1") (pintype "passive"))
    )
    (net (code "63") (name "Net-(Q9-G2)") (class "Default")
      (node (ref "C21") (pin "2") (pinfunction "2_2") (pintype "passive"))
      (node (ref "Q9") (pin "8") (pinfunction "G2_8") (pintype "passive"))
      (node (ref "R41") (pin "1") (pinfunction "1_1") (pintype "passive"))
      (node (ref "R42") (pin "1") (pinfunction "1_1") (pintype "passive"))
    )
    (net (code "64") (name "Net-(R5-Pad2)") (class "Default")
      (node (ref "R5") (pin "2") (pinfunction "2_2") (pintype "passive"))
      (node (ref "R9") (pin "1") (pinfunction "1_1") (pintype "passive"))
    )
    (net (code "65") (name "Net-(U1-FB)") (class "Default")
      (node (ref "C7") (pin "1") (pinfunction "1_1") (pintype "passive"))
      (node (ref "R2") (pin "2") (pinfunction "2_2") (pintype "passive"))
      (node (ref "R5") (pin "1") (pinfunction "1_1") (pintype "passive"))
      (node (ref "U1") (pin "3") (pinfunction "FB_3") (pintype "passive"))
    )
    (net (code "66") (name "Net-(U1-GVDD)") (class "Default")
      (node (ref "C1") (pin "2") (pinfunction "2_2") (pintype "passive"))
      (node (ref "U1") (pin "1") (pinfunction "GVDD_1") (pintype "passive"))
    )
    (net (code "67") (name "Net-(U1-LX)") (class "Default")
      (node (ref "L1") (pin "1") (pinfunction "1_1") (pintype "passive"))
      (node (ref "U1") (pin "6") (pinfunction "LX_6") (pintype "passive"))
    )
    (net (code "68") (name "Net-(U2-ICHG)") (class "Default")
      (node (ref "R3") (pin "1") (pinfunction "1_1") (pintype "passive"))
      (node (ref "U2") (pin "6") (pinfunction "ICHG_6") (pintype "passive"))
    )
    (net (code "69") (name "Net-(U2-NTC)") (class "Default")
      (node (ref "R11") (pin "1") (pinfunction "1_1") (pintype "passive"))
      (node (ref "R7") (pin "2") (pinfunction "2_2") (pintype "passive"))
      (node (ref "U2") (pin "7") (pinfunction "NTC_7") (pintype "passive"))
    )
    (net (code "70") (name "Net-(U4-AVDD)") (class "Default")
      (node (ref "C29") (pin "2") (pinfunction "2_2") (pintype "passive"))
      (node (ref "U4") (pin "3") (pinfunction "AVDD_3") (pintype "passive"))
    )
    (net (code "71") (name "Net-(U4-P0.2{slash}RSTN)") (class "Default")
      (node (ref "C28") (pin "1") (pinfunction "1_1") (pintype "passive"))
      (node (ref "U4") (pin "2") (pinfunction "P0.2/RSTN_2") (pintype "passive"))
    )
    (net (code "72") (name "PGND") (class "Default")
      (node (ref "C13") (pin "1") (pinfunction "1_1") (pintype "passive"))
      (node (ref "C18") (pin "1") (pinfunction "1_1") (pintype "passive"))
      (node (ref "C21") (pin "1") (pinfunction "1_1") (pintype "passive"))
      (node (ref "FU1") (pin "2") (pinfunction "2_2") (pintype "passive"))
      (node (ref "Q1") (pin "5") (pinfunction "S2_5") (pintype "passive"))
      (node (ref "Q1") (pin "6") (pinfunction "S2_6") (pintype "passive"))
      (node (ref "Q1") (pin "7") (pinfunction "S2_7") (pintype "passive"))
      (node (ref "Q2") (pin "5") (pinfunction "S2_5") (pintype "passive"))
      (node (ref "Q2") (pin "6") (pinfunction "S2_6") (pintype "passive"))
      (node (ref "Q2") (pin "7") (pinfunction "S2_7") (pintype "passive"))
      (node (ref "Q9") (pin "5") (pinfunction "S2_5") (pintype "passive"))
      (node (ref "Q9") (pin "6") (pinfunction "S2_6") (pintype "passive"))
      (node (ref "Q9") (pin "7") (pinfunction "S2_7") (pintype "passive"))
      (node (ref "R12") (pin "2") (pinfunction "2_2") (pintype "passive"))
      (node (ref "R26") (pin "2") (pinfunction "2_2") (pintype "passive"))
      (node (ref "R42") (pin "2") (pinfunction "2_2") (pintype "passive"))
      (node (ref "R45") (pin "1") (pinfunction "1_1") (pintype "passive"))
      (node (ref "R48") (pin "1") (pinfunction "1_1") (pintype "passive"))
      (node (ref "R49") (pin "1") (pinfunction "1_1") (pintype "passive"))
    )
    (net (code "73") (name "VBAT_8V4") (class "Default")
      (node (ref "C14") (pin "2") (pinfunction "2_2") (pintype "passive"))
      (node (ref "C15") (pin "2") (pinfunction "2_2") (pintype "passive"))
      (node (ref "C6") (pin "2") (pinfunction "2_2") (pintype "passive"))
      (node (ref "DS1") (pin "1") (pinfunction "A_1") (pintype "passive"))
      (node (ref "P1") (pin "3") (pinfunction "3_3") (pintype "passive"))
      (node (ref "Q1") (pin "2") (pinfunction "D1_2") (pintype "passive"))
      (node (ref "Q1") (pin "3") (pinfunction "D1_3") (pintype "passive"))
      (node (ref "Q1") (pin "4") (pinfunction "D1_4") (pintype "passive"))
      (node (ref "Q1") (pin "9") (pinfunction "D1_9") (pintype "passive"))
      (node (ref "Q2") (pin "2") (pinfunction "D1_2") (pintype "passive"))
      (node (ref "Q2") (pin "3") (pinfunction "D1_3") (pintype "passive"))
      (node (ref "Q2") (pin "4") (pinfunction "D1_4") (pintype "passive"))
      (node (ref "Q2") (pin "9") (pinfunction "D1_9") (pintype "passive"))
      (node (ref "Q9") (pin "2") (pinfunction "D1_2") (pintype "passive"))
      (node (ref "Q9") (pin "3") (pinfunction "D1_3") (pintype "passive"))
      (node (ref "Q9") (pin "4") (pinfunction "D1_4") (pintype "passive"))
      (node (ref "Q9") (pin "9") (pinfunction "D1_9") (pintype "passive"))
      (node (ref "R13") (pin "1") (pinfunction "1_1") (pintype "passive"))
      (node (ref "R44") (pin "1") (pinfunction "1_1") (pintype "passive"))
      (node (ref "R8") (pin "2") (pinfunction "2_2") (pintype "passive"))
      (node (ref "U1") (pin "5") (pinfunction "VIN_5") (pintype "passive"))
      (node (ref "U2") (pin "5") (pinfunction "BAT_5") (pintype "passive"))
      (node (ref "U4") (pin "27") (pinfunction "VCC_27") (pintype "passive"))
    )
    (net (code "74") (name "unconnected-(U4-GND-Pad17)") (class "Default")
      (node (ref "U4") (pin "17") (pinfunction "GND_17") (pintype "passive+no_connect"))
    )
    (net (code "75") (name "unconnected-(U4-MCPWM_CH5N{slash}SPI_DO{slash}SDA{slash}P2.10-Pad34)") (class "Default")
      (node (ref "U4") (pin "34") (pinfunction "MCPWM_CH5N/SPI_DO/SDA/P2.10_34") (pintype "passive+no_connect"))
    )
    (net (code "76") (name "unconnected-(U4-OPA3_IN{slash}P3.14-Pad35)") (class "Default")
      (node (ref "U4") (pin "35") (pinfunction "OPA3_IN/P3.14_35") (pintype "passive+no_connect"))
    )
    (net (code "77") (name "unconnected-(U4-P0.15{slash}CMP2_OUT{slash}MCPWM_CH0P{slash}UART0_RXD{slash}SPI_DO{slash}SDA{slash}TIM0_CH0{slash}CMP0_IN-Pad12)") (class "Default")
      (node (ref "U4") (pin "12") (pinfunction "P0.15/CMP2_OUT/MCPWM_CH0P/UART0_RXD/SPI_DO/SDA/TIM0_CH0/CMP0_IN_12") (pintype "passive+no_connect"))
    )
    (net (code "78") (name "unconnected-(U4-P1.0{slash}MCPWM_CH0N{slash}UART0_TXD{slash}SPI_DI-Pad13)") (class "Default")
      (node (ref "U4") (pin "13") (pinfunction "P1.0/MCPWM_CH0N/UART0_TXD/SPI_DI_13") (pintype "passive+no_connect"))
    )
    (net (code "79") (name "unconnected-(U4-P2.7{slash}UART0_TXD{slash}TIM0_CH0{slash}TIM3_CH1{slash}CLUOUT1{slash}ADC0_CH11{slash}OPAx_OUT{slash}LDO15{slash}REF-Pad16)") (class "Default")
      (node (ref "U4") (pin "16") (pinfunction "P2.7/UART0_TXD/TIM0_CH0/TIM3_CH1/CLUOUT1/ADC0_CH11/OPAx_OUT/LDO15/REF_16") (pintype "passive+no_connect"))
    )
    (net (code "80") (name "unconnected-(U4-P3.5{slash}OPA0_IP-Pad14)") (class "Default")
      (node (ref "U4") (pin "14") (pinfunction "P3.5/OPA0_IP_14") (pintype "passive"))
    )
    (net (code "81") (name "unconnected-(U4-P3.7{slash}OPA0_IN-Pad15)") (class "Default")
      (node (ref "U4") (pin "15") (pinfunction "P3.7/OPA0_IN_15") (pintype "passive"))
    )
  )
)
